# sonars.net
KiCad netlist of a schematic drawn in EAGLE
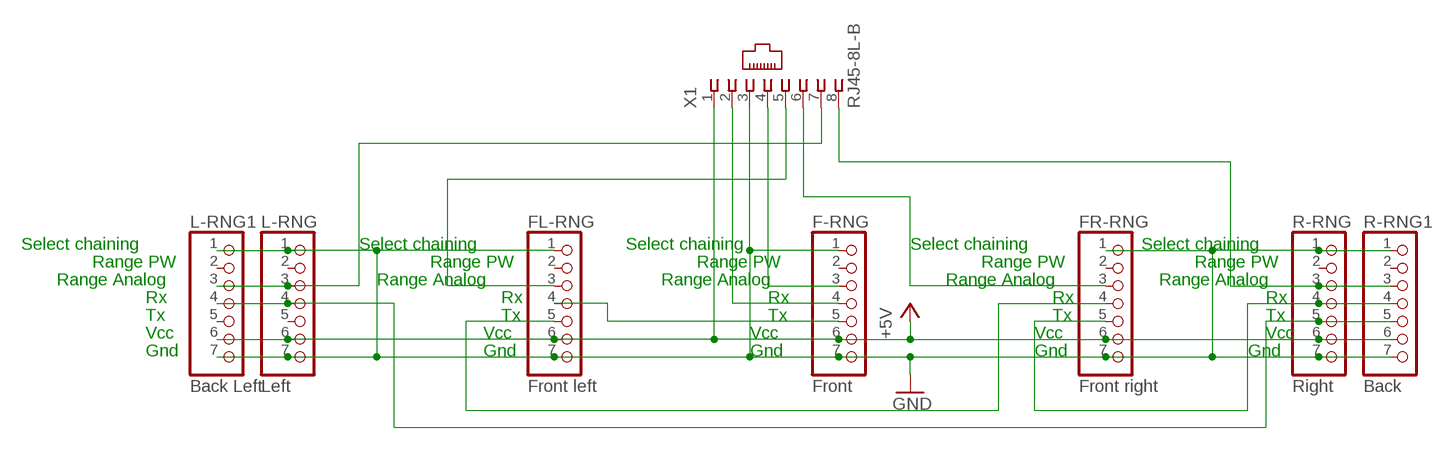
[diagram p0: schematic, sheet 1]

(export (version "E")
  (design (tool "Eeschema 10.0.6"))
  (components
    (comp (ref "F-RNG")
      (value "Front")
      (footprint "eagle-import:1X07")
      (libsource (lib "eagle-import") (part "PINHD-1X7"))
    )
    (comp (ref "FL-RNG")
      (value "Front left")
      (footprint "eagle-import:1X07")
      (libsource (lib "eagle-import") (part "PINHD-1X7"))
    )
    (comp (ref "FR-RNG")
      (value "Front right")
      (footprint "eagle-import:1X07")
      (libsource (lib "eagle-import") (part "PINHD-1X7"))
    )
    (comp (ref "L-RNG")
      (value "Left")
      (footprint "eagle-import:1X07")
      (libsource (lib "eagle-import") (part "PINHD-1X7"))
    )
    (comp (ref "L-RNG1")
      (value "Back Left")
      (footprint "eagle-import:1X07")
      (libsource (lib "eagle-import") (part "PINHD-1X7"))
    )
    (comp (ref "R-RNG")
      (value "Right")
      (footprint "eagle-import:1X07")
      (libsource (lib "eagle-import") (part "PINHD-1X7"))
    )
    (comp (ref "R-RNG1")
      (value "Back")
      (footprint "eagle-import:1X07")
      (libsource (lib "eagle-import") (part "PINHD-1X7"))
    )
    (comp (ref "X1")
      (value "RJ45-8L-B")
      (footprint "eagle-import:RJ45-NO-SHIELD")
      (fields (field (name "MF") "TYCO ELECTRONICS"))
      (libsource (lib "eagle-import") (part "RJ45-8L-B"))
    )
  )
  (nets
    (net (code "1") (name "+5V") (class "Default")
      (node (ref "F-RNG") (pin "6") (pinfunction "6_6") (pintype "passive"))
      (node (ref "FL-RNG") (pin "6") (pinfunction "6_6") (pintype "passive"))
      (node (ref "FR-RNG") (pin "6") (pinfunction "6_6") (pintype "passive"))
      (node (ref "L-RNG") (pin "6") (pinfunction "6_6") (pintype "passive"))
      (node (ref "L-RNG1") (pin "6") (pinfunction "6_6") (pintype "passive"))
      (node (ref "R-RNG") (pin "6") (pinfunction "6_6") (pintype "passive"))
      (node (ref "R-RNG1") (pin "6") (pinfunction "6_6") (pintype "passive"))
      (node (ref "X1") (pin "1") (pinfunction "1_1") (pintype "passive"))
    )
    (net (code "2") (name "GND") (class "Default")
      (node (ref "F-RNG") (pin "1") (pinfunction "1_1") (pintype "passive"))
      (node (ref "F-RNG") (pin "7") (pinfunction "7_7") (pintype "passive"))
      (node (ref "FL-RNG") (pin "1") (pinfunction "1_1") (pintype "passive"))
      (node (ref "FL-RNG") (pin "7") (pinfunction "7_7") (pintype "passive"))
      (node (ref "FR-RNG") (pin "1") (pinfunction "1_1") (pintype "passive"))
      (node (ref "FR-RNG") (pin "7") (pinfunction "7_7") (pintype "passive"))
      (node (ref "L-RNG") (pin "1") (pinfunction "1_1") (pintype "passive"))
      (node (ref "L-RNG") (pin "7") (pinfunction "7_7") (pintype "passive"))
      (node (ref "L-RNG1") (pin "1") (pinfunction "1_1") (pintype "passive"))
      (node (ref "L-RNG1") (pin "7") (pinfunction "7_7") (pintype "passive"))
      (node (ref "R-RNG") (pin "1") (pinfunction "1_1") (pintype "passive"))
      (node (ref "R-RNG") (pin "7") (pinfunction "7_7") (pintype "passive"))
      (node (ref "R-RNG1") (pin "1") (pinfunction "1_1") (pintype "passive"))
      (node (ref "R-RNG1") (pin "7") (pinfunction "7_7") (pintype "passive"))
      (node (ref "X1") (pin "3") (pinfunction "3_3") (pintype "passive"))
    )
    (net (code "3") (name "Net-(F-RNG-Pad3)") (class "Default")
      (node (ref "F-RNG") (pin "3") (pinfunction "3_3") (pintype "passive"))
      (node (ref "X1") (pin "4") (pinfunction "4_4") (pintype "passive"))
    )
    (net (code "4") (name "Net-(F-RNG-Pad4)") (class "Default")
      (node (ref "F-RNG") (pin "4") (pinfunction "4_4") (pintype "passive"))
      (node (ref "X1") (pin "2") (pinfunction "2_2") (pintype "passive"))
    )
    (net (code "5") (name "Net-(F-RNG-Pad5)") (class "Default")
      (node (ref "F-RNG") (pin "5") (pinfunction "5_5") (pintype "passive"))
      (node (ref "FL-RNG") (pin "4") (pinfunction "4_4") (pintype "passive"))
    )
    (net (code "6") (name "Net-(FL-RNG-Pad3)") (class "Default")
      (node (ref "FL-RNG") (pin "3") (pinfunction "3_3") (pintype "passive"))
      (node (ref "X1") (pin "5") (pinfunction "5_5") (pintype "passive"))
    )
    (net (code "7") (name "Net-(FL-RNG-Pad5)") (class "Default")
      (node (ref "FL-RNG") (pin "5") (pinfunction "5_5") (pintype "passive"))
      (node (ref "FR-RNG") (pin "4") (pinfunction "4_4") (pintype "passive"))
    )
    (net (code "8") (name "Net-(FR-RNG-Pad3)") (class "Default")
      (node (ref "FR-RNG") (pin "3") (pinfunction "3_3") (pintype "passive"))
      (node (ref "X1") (pin "6") (pinfunction "6_6") (pintype "passive"))
    )
    (net (code "9") (name "Net-(FR-RNG-Pad5)") (class "Default")
      (node (ref "FR-RNG") (pin "5") (pinfunction "5_5") (pintype "passive"))
      (node (ref "R-RNG") (pin "4") (pinfunction "4_4") (pintype "passive"))
      (node (ref "R-RNG1") (pin "4") (pinfunction "4_4") (pintype "passive"))
    )
    (net (code "10") (name "Net-(L-RNG-Pad3)") (class "Default")
      (node (ref "L-RNG") (pin "3") (pinfunction "3_3") (pintype "passive"))
      (node (ref "L-RNG1") (pin "3") (pinfunction "3_3") (pintype "passive"))
      (node (ref "X1") (pin "7") (pinfunction "7_7") (pintype "passive"))
    )
    (net (code "11") (name "Net-(L-RNG-Pad4)") (class "Default")
      (node (ref "L-RNG") (pin "4") (pinfunction "4_4") (pintype "passive"))
      (node (ref "L-RNG1") (pin "4") (pinfunction "4_4") (pintype "passive"))
      (node (ref "R-RNG") (pin "5") (pinfunction "5_5") (pintype "passive"))
      (node (ref "R-RNG1") (pin "5") (pinfunction "5_5") (pintype "passive"))
    )
    (net (code "12") (name "Net-(R-RNG-Pad3)") (class "Default")
      (node (ref "R-RNG") (pin "3") (pinfunction "3_3") (pintype "passive"))
      (node (ref "R-RNG1") (pin "3") (pinfunction "3_3") (pintype "passive"))
      (node (ref "X1") (pin "8") (pinfunction "8_8") (pintype "passive"))
    )
    (net (code "13") (name "unconnected-(F-RNG-Pad2)") (class "Default")
      (node (ref "F-RNG") (pin "2") (pinfunction "2_2") (pintype "passive"))
    )
    (net (code "14") (name "unconnected-(FL-RNG-Pad2)") (class "Default")
      (node (ref "FL-RNG") (pin "2") (pinfunction "2_2") (pintype "passive"))
    )
    (net (code "15") (name "unconnected-(FR-RNG-Pad2)") (class "Default")
      (node (ref "FR-RNG") (pin "2") (pinfunction "2_2") (pintype "passive"))
    )
    (net (code "16") (name "unconnected-(L-RNG-Pad2)") (class "Default")
      (node (ref "L-RNG") (pin "2") (pinfunction "2_2") (pintype "passive"))
    )
    (net (code "17") (name "unconnected-(L-RNG-Pad5)") (class "Default")
      (node (ref "L-RNG") (pin "5") (pinfunction "5_5") (pintype "passive"))
    )
    (net (code "18") (name "unconnected-(L-RNG1-Pad2)") (class "Default")
      (node (ref "L-RNG1") (pin "2") (pinfunction "2_2") (pintype "passive"))
    )
    (net (code "19") (name "unconnected-(L-RNG1-Pad5)") (class "Default")
      (node (ref "L-RNG1") (pin "5") (pinfunction "5_5") (pintype "passive"))
    )
    (net (code "20") (name "unconnected-(R-RNG-Pad2)") (class "Default")
      (node (ref "R-RNG") (pin "2") (pinfunction "2_2") (pintype "passive"))
    )
    (net (code "21") (name "unconnected-(R-RNG1-Pad2)") (class "Default")
      (node (ref "R-RNG1") (pin "2") (pinfunction "2_2") (pintype "passive"))
    )
  )
)
